# Nguyen_Quang_Minh.net
KiCad netlist of a schematic drawn in Altium Designer
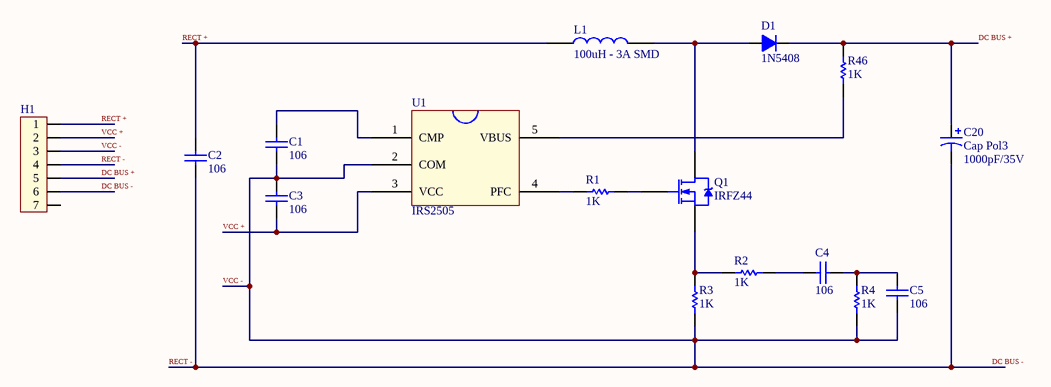
[diagram p0: Nguyen Quang Minh.SchDoc]

(export (version "E")
  (design (tool "Eeschema 10.0.6"))
  (components
    (comp (ref "C1")
      (value "106")
      (footprint "tu 1206")
      (description "Dán")
      (libsource (lib "Tu dien") (part "Tu 1206 106 16V 20%"))
    )
    (comp (ref "C2")
      (value "106")
      (footprint "tu 1206")
      (description "Dán")
      (libsource (lib "Tu dien") (part "Tu 1206 106 16V 20%"))
    )
    (comp (ref "C3")
      (value "106")
      (footprint "tu 1206")
      (description "Dán")
      (libsource (lib "Tu dien") (part "Tu 1206 106 16V 20%"))
    )
    (comp (ref "C4")
      (value "106")
      (footprint "tu 1206")
      (description "Dán")
      (libsource (lib "Tu dien") (part "Tu 1206 106 16V 20%"))
    )
    (comp (ref "C5")
      (value "106")
      (footprint "tu 1206")
      (description "Dán")
      (libsource (lib "Tu dien") (part "Tu 1206 106 16V 20%"))
    )
    (comp (ref "C20")
      (value "Cap Pol3")
      (footprint "CP2/5")
      (description "Polarized Capacitor (Surface Mount)")
      (fields (field (name "ALTIUM_VALUE") "1000pF/35V") (field (name "PUBLISHER") "Altium Limited"))
      (libsource (lib "syhaunguyen") (part "Cap Pol3_2"))
    )
    (comp (ref "D1")
      (value "1N5408")
      (footprint "D5A")
      (description "Diode 5A")
      (libsource (lib "syhaunguyen") (part "D5A"))
    )
    (comp (ref "H1")
      (value "Header 7P 2.54 Duc Thang")
      (footprint "XH2.54M-7")
      (description "Cắm")
      (libsource (lib "Header") (part "Header 7P 2.54 Duc Thang"))
    )
    (comp (ref "L1")
      (value "100uH - 3A SMD")
      (footprint "Cuon Cam 12x12x10")
      (description "Dán")
      (libsource (lib "Cuon Cam") (part "CUON CAM 100uH SMD"))
    )
    (comp (ref "Q1")
      (value "IRFZ44")
      (footprint "TO220")
      (description "N-Channel Power MOSFET")
      (libsource (lib "TranFet") (part "IRFZ44 DIP"))
    )
    (comp (ref "R1")
      (value "1K")
      (footprint "R1/4W")
      (description "Resistor")
      (fields
        (field (name "MANUFACTURER") "Generic Components")
        (field (name "Comment") "Res1")
        (field (name "PUBLISHER") "Altium Hobart Technology Centre")
      )
      (libsource (lib "syhaunguyen") (part "Res1_1"))
    )
    (comp (ref "R2")
      (value "1K")
      (footprint "R1/4W")
      (description "Resistor")
      (fields
        (field (name "MANUFACTURER") "Generic Components")
        (field (name "Comment") "Res1")
        (field (name "PUBLISHER") "Altium Hobart Technology Centre")
      )
      (libsource (lib "syhaunguyen") (part "Res1_1"))
    )
    (comp (ref "R3")
      (value "1K")
      (footprint "R1/4W")
      (description "Resistor")
      (fields
        (field (name "MANUFACTURER") "Generic Components")
        (field (name "Comment") "Res1")
        (field (name "PUBLISHER") "Altium Hobart Technology Centre")
      )
      (libsource (lib "syhaunguyen") (part "Res1_1"))
    )
    (comp (ref "R4")
      (value "1K")
      (footprint "R1/4W")
      (description "Resistor")
      (fields
        (field (name "MANUFACTURER") "Generic Components")
        (field (name "Comment") "Res1")
        (field (name "PUBLISHER") "Altium Hobart Technology Centre")
      )
      (libsource (lib "syhaunguyen") (part "Res1_1"))
    )
    (comp (ref "R46")
      (value "1K")
      (footprint "R1/4W")
      (description "Resistor")
      (fields
        (field (name "MANUFACTURER") "Generic Components")
        (field (name "Comment") "Res1")
        (field (name "PUBLISHER") "Altium Hobart Technology Centre")
      )
      (libsource (lib "syhaunguyen") (part "Res1_1"))
    )
    (comp (ref "U1")
      (value "IRS2505")
      (footprint "IRS2505")
      (libsource (lib "Nguyen Quang Minh") (part "IRS2505"))
    )
  )
  (nets
    (net (code "1") (name "/DC BUS +") (class "Default")
      (node (ref "C20") (pin "1") (pinfunction "1_1") (pintype "passive"))
      (node (ref "D1") (pin "2") (pinfunction "K_2") (pintype "passive"))
      (node (ref "H1") (pin "5") (pinfunction "5_5") (pintype "passive"))
      (node (ref "R46") (pin "2") (pinfunction "2_2") (pintype "passive"))
    )
    (net (code "2") (name "/DC BUS -") (class "Default")
      (node (ref "C1") (pin "2") (pinfunction "2_2") (pintype "passive"))
      (node (ref "C2") (pin "2") (pinfunction "2_2") (pintype "passive"))
      (node (ref "C20") (pin "2") (pinfunction "2_2") (pintype "passive"))
      (node (ref "C3") (pin "1") (pinfunction "1_1") (pintype "passive"))
      (node (ref "C5") (pin "2") (pinfunction "2_2") (pintype "passive"))
      (node (ref "H1") (pin "3") (pinfunction "3_3") (pintype "passive"))
      (node (ref "H1") (pin "4") (pinfunction "4_4") (pintype "passive"))
      (node (ref "H1") (pin "6") (pinfunction "6_6") (pintype "passive"))
      (node (ref "R3") (pin "2") (pinfunction "2_2") (pintype "passive"))
      (node (ref "R4") (pin "2") (pinfunction "2_2") (pintype "passive"))
      (node (ref "U1") (pin "2") (pinfunction "COM_2") (pintype "passive"))
    )
    (net (code "3") (name "/RECT +") (class "Default")
      (node (ref "C2") (pin "1") (pinfunction "1_1") (pintype "passive"))
      (node (ref "H1") (pin "1") (pinfunction "1_1") (pintype "passive"))
      (node (ref "L1") (pin "1") (pinfunction "1_1") (pintype "passive"))
    )
    (net (code "4") (name "/VCC +") (class "Default")
      (node (ref "C3") (pin "2") (pinfunction "2_2") (pintype "passive"))
      (node (ref "H1") (pin "2") (pinfunction "2_2") (pintype "passive"))
      (node (ref "U1") (pin "3") (pinfunction "VCC_3") (pintype "passive"))
    )
    (net (code "5") (name "Net-(C4-Pad1)") (class "Default")
      (node (ref "C4") (pin "1") (pinfunction "1_1") (pintype "passive"))
      (node (ref "R2") (pin "1") (pinfunction "1_1") (pintype "passive"))
    )
    (net (code "6") (name "Net-(C4-Pad2)") (class "Default")
      (node (ref "C4") (pin "2") (pinfunction "2_2") (pintype "passive"))
      (node (ref "C5") (pin "1") (pinfunction "1_1") (pintype "passive"))
      (node (ref "R4") (pin "1") (pinfunction "1_1") (pintype "passive"))
    )
    (net (code "7") (name "Net-(D1-A)") (class "Default")
      (node (ref "D1") (pin "1") (pinfunction "A_1") (pintype "passive"))
      (node (ref "L1") (pin "2") (pinfunction "2_2") (pintype "passive"))
      (node (ref "Q1") (pin "2") (pinfunction "D_2") (pintype "passive"))
    )
    (net (code "8") (name "Net-(Q1-G)") (class "Default")
      (node (ref "Q1") (pin "1") (pinfunction "G_1") (pintype "passive"))
      (node (ref "R1") (pin "1") (pinfunction "1_1") (pintype "passive"))
    )
    (net (code "9") (name "Net-(Q1-S)") (class "Default")
      (node (ref "Q1") (pin "3") (pinfunction "S_3") (pintype "passive"))
      (node (ref "R2") (pin "2") (pinfunction "2_2") (pintype "passive"))
      (node (ref "R3") (pin "1") (pinfunction "1_1") (pintype "passive"))
    )
    (net (code "10") (name "Net-(U1-CMP)") (class "Default")
      (node (ref "C1") (pin "1") (pinfunction "1_1") (pintype "passive"))
      (node (ref "U1") (pin "1") (pinfunction "CMP_1") (pintype "passive"))
    )
    (net (code "11") (name "Net-(U1-PFC)") (class "Default")
      (node (ref "R1") (pin "2") (pinfunction "2_2") (pintype "passive"))
      (node (ref "U1") (pin "4") (pinfunction "PFC_4") (pintype "passive"))
    )
    (net (code "12") (name "Net-(U1-VBUS)") (class "Default")
      (node (ref "R46") (pin "1") (pinfunction "1_1") (pintype "passive"))
      (node (ref "U1") (pin "5") (pinfunction "VBUS_5") (pintype "passive"))
    )
    (net (code "13") (name "unconnected-(H1-Pad7)") (class "Default")
      (node (ref "H1") (pin "7") (pinfunction "7_7") (pintype "passive"))
    )
  )
)
